# Demo_Board_4_-_Schematic.net
KiCad netlist of a schematic drawn in Altium Designer
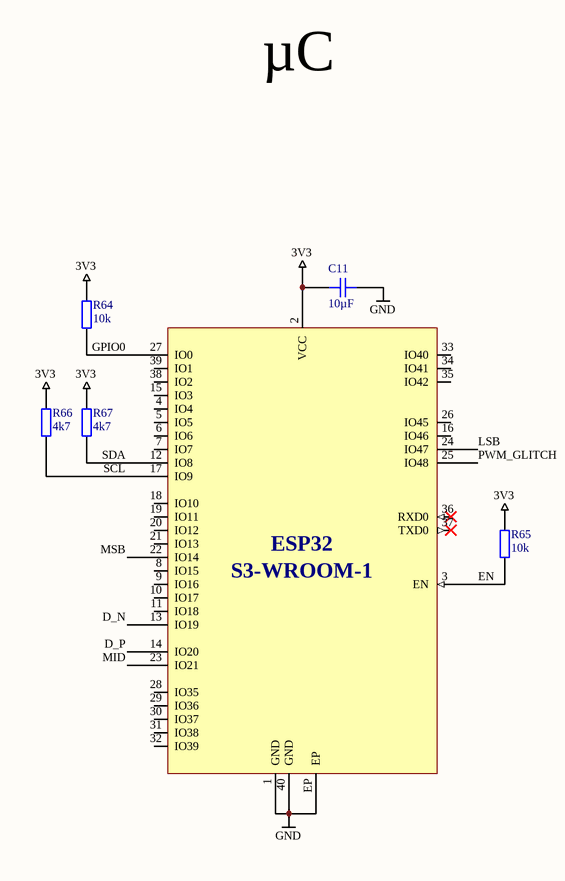
[diagram p0: Demo Board 4 - Schematic.SchDoc]

(export (version "E")
  (design (tool "Eeschema 10.0.6"))
  (components
    (comp (ref "C11")
      (value "10µF")
      (footprint "CAP_0805")
      (description "Capacitor SMD 0805")
      (libsource (lib "Auer Library") (part "CAP_0805"))
    )
    (comp (ref "R64")
      (value "10k")
      (footprint "RES_0603")
      (description "Resistor SMD 0603")
      (libsource (lib "Auer Library") (part "RES_0603"))
    )
    (comp (ref "R65")
      (value "10k")
      (footprint "RES_0603")
      (description "Resistor SMD 0603")
      (libsource (lib "Auer Library") (part "RES_0603"))
    )
    (comp (ref "R66")
      (value "4k7")
      (footprint "RES_0603")
      (description "Resistor SMD 0603")
      (libsource (lib "Auer Library") (part "RES_0603"))
    )
    (comp (ref "R67")
      (value "4k7")
      (footprint "RES_0603")
      (description "Resistor SMD 0603")
      (libsource (lib "Auer Library") (part "RES_0603"))
    )
    (comp (ref "U3")
      (value "ESP32-S3-WROOM-1-N8")
      (footprint "ESP32-S3-WROOM-1")
      (fields
        (field (name "MANUFACTURER") "Espressif")
        (field (name "MANUFACTURER PART NUMBER") "ESP32-S3-WROOM-1-N4")
      )
      (libsource (lib "Auer Library") (part "ESP32-S3-WROOM-1-N4"))
    )
  )
  (nets
    (net (code "1") (name "/D_N") (class "Default")
      (node (ref "U3") (pin "13") (pinfunction "IO19_13") (pintype "bidirectional"))
    )
    (net (code "2") (name "/D_P") (class "Default")
      (node (ref "U3") (pin "14") (pinfunction "IO20_14") (pintype "bidirectional"))
    )
    (net (code "3") (name "/EN") (class "Default")
      (node (ref "R65") (pin "1") (pinfunction "1_1") (pintype "passive"))
      (node (ref "U3") (pin "3") (pinfunction "EN_3") (pintype "input"))
    )
    (net (code "4") (name "/GPIO0") (class "Default")
      (node (ref "R64") (pin "1") (pinfunction "1_1") (pintype "passive"))
      (node (ref "U3") (pin "27") (pinfunction "IO0_27") (pintype "bidirectional"))
    )
    (net (code "5") (name "/LSB") (class "Default")
      (node (ref "U3") (pin "24") (pinfunction "IO47_24") (pintype "bidirectional"))
    )
    (net (code "6") (name "/MID") (class "Default")
      (node (ref "U3") (pin "23") (pinfunction "IO21_23") (pintype "bidirectional"))
    )
    (net (code "7") (name "/MSB") (class "Default")
      (node (ref "U3") (pin "22") (pinfunction "IO14_22") (pintype "bidirectional"))
    )
    (net (code "8") (name "/PWM_GLITCH") (class "Default")
      (node (ref "U3") (pin "25") (pinfunction "IO48_25") (pintype "bidirectional"))
    )
    (net (code "9") (name "/SCL") (class "Default")
      (node (ref "R66") (pin "1") (pinfunction "1_1") (pintype "passive"))
      (node (ref "U3") (pin "17") (pinfunction "IO9_17") (pintype "bidirectional"))
    )
    (net (code "10") (name "/SDA") (class "Default")
      (node (ref "R67") (pin "1") (pinfunction "1_1") (pintype "passive"))
      (node (ref "U3") (pin "12") (pinfunction "IO8_12") (pintype "bidirectional"))
    )
    (net (code "11") (name "3V3") (class "Default")
      (node (ref "C11") (pin "2") (pinfunction "2_2") (pintype "passive"))
      (node (ref "R64") (pin "2") (pinfunction "2_2") (pintype "passive"))
      (node (ref "R65") (pin "2") (pinfunction "2_2") (pintype "passive"))
      (node (ref "R66") (pin "2") (pinfunction "2_2") (pintype "passive"))
      (node (ref "R67") (pin "2") (pinfunction "2_2") (pintype "passive"))
      (node (ref "U3") (pin "2") (pinfunction "VCC_2") (pintype "power_in"))
    )
    (net (code "12") (name "GND") (class "Default")
      (node (ref "C11") (pin "1") (pinfunction "1_1") (pintype "passive"))
      (node (ref "U3") (pin "1") (pinfunction "GND_1") (pintype "power_in"))
      (node (ref "U3") (pin "40") (pinfunction "GND_40") (pintype "power_in"))
      (node (ref "U3") (pin "EP") (pinfunction "EP_EP") (pintype "power_in"))
    )
    (net (code "13") (name "unconnected-(U3-IO1-Pad39)") (class "Default")
      (node (ref "U3") (pin "39") (pinfunction "IO1_39") (pintype "bidirectional"))
    )
    (net (code "14") (name "unconnected-(U3-IO2-Pad38)") (class "Default")
      (node (ref "U3") (pin "38") (pinfunction "IO2_38") (pintype "bidirectional"))
    )
    (net (code "15") (name "unconnected-(U3-IO3-Pad15)") (class "Default")
      (node (ref "U3") (pin "15") (pinfunction "IO3_15") (pintype "bidirectional"))
    )
    (net (code "16") (name "unconnected-(U3-IO4-Pad4)") (class "Default")
      (node (ref "U3") (pin "4") (pinfunction "IO4_4") (pintype "bidirectional"))
    )
    (net (code "17") (name "unconnected-(U3-IO5-Pad5)") (class "Default")
      (node (ref "U3") (pin "5") (pinfunction "IO5_5") (pintype "bidirectional"))
    )
    (net (code "18") (name "unconnected-(U3-IO6-Pad6)") (class "Default")
      (node (ref "U3") (pin "6") (pinfunction "IO6_6") (pintype "bidirectional"))
    )
    (net (code "19") (name "unconnected-(U3-IO7-Pad7)") (class "Default")
      (node (ref "U3") (pin "7") (pinfunction "IO7_7") (pintype "bidirectional"))
    )
    (net (code "20") (name "unconnected-(U3-IO10-Pad18)") (class "Default")
      (node (ref "U3") (pin "18") (pinfunction "IO10_18") (pintype "bidirectional"))
    )
    (net (code "21") (name "unconnected-(U3-IO11-Pad19)") (class "Default")
      (node (ref "U3") (pin "19") (pinfunction "IO11_19") (pintype "bidirectional"))
    )
    (net (code "22") (name "unconnected-(U3-IO12-Pad20)") (class "Default")
      (node (ref "U3") (pin "20") (pinfunction "IO12_20") (pintype "bidirectional"))
    )
    (net (code "23") (name "unconnected-(U3-IO13-Pad21)") (class "Default")
      (node (ref "U3") (pin "21") (pinfunction "IO13_21") (pintype "bidirectional"))
    )
    (net (code "24") (name "unconnected-(U3-IO15-Pad8)") (class "Default")
      (node (ref "U3") (pin "8") (pinfunction "IO15_8") (pintype "bidirectional"))
    )
    (net (code "25") (name "unconnected-(U3-IO16-Pad9)") (class "Default")
      (node (ref "U3") (pin "9") (pinfunction "IO16_9") (pintype "bidirectional"))
    )
    (net (code "26") (name "unconnected-(U3-IO17-Pad10)") (class "Default")
      (node (ref "U3") (pin "10") (pinfunction "IO17_10") (pintype "bidirectional"))
    )
    (net (code "27") (name "unconnected-(U3-IO18-Pad11)") (class "Default")
      (node (ref "U3") (pin "11") (pinfunction "IO18_11") (pintype "bidirectional"))
    )
    (net (code "28") (name "unconnected-(U3-IO35-Pad28)") (class "Default")
      (node (ref "U3") (pin "28") (pinfunction "IO35_28") (pintype "bidirectional"))
    )
    (net (code "29") (name "unconnected-(U3-IO36-Pad29)") (class "Default")
      (node (ref "U3") (pin "29") (pinfunction "IO36_29") (pintype "bidirectional"))
    )
    (net (code "30") (name "unconnected-(U3-IO37-Pad30)") (class "Default")
      (node (ref "U3") (pin "30") (pinfunction "IO37_30") (pintype "bidirectional"))
    )
    (net (code "31") (name "unconnected-(U3-IO38-Pad31)") (class "Default")
      (node (ref "U3") (pin "31") (pinfunction "IO38_31") (pintype "bidirectional"))
    )
    (net (code "32") (name "unconnected-(U3-IO39-Pad32)") (class "Default")
      (node (ref "U3") (pin "32") (pinfunction "IO39_32") (pintype "bidirectional"))
    )
    (net (code "33") (name "unconnected-(U3-IO40-Pad33)") (class "Default")
      (node (ref "U3") (pin "33") (pinfunction "IO40_33") (pintype "bidirectional"))
    )
    (net (code "34") (name "unconnected-(U3-IO41-Pad34)") (class "Default")
      (node (ref "U3") (pin "34") (pinfunction "IO41_34") (pintype "bidirectional"))
    )
    (net (code "35") (name "unconnected-(U3-IO42-Pad35)") (class "Default")
      (node (ref "U3") (pin "35") (pinfunction "IO42_35") (pintype "bidirectional"))
    )
    (net (code "36") (name "unconnected-(U3-IO45-Pad26)") (class "Default")
      (node (ref "U3") (pin "26") (pinfunction "IO45_26") (pintype "bidirectional"))
    )
    (net (code "37") (name "unconnected-(U3-IO46-Pad16)") (class "Default")
      (node (ref "U3") (pin "16") (pinfunction "IO46_16") (pintype "bidirectional"))
    )
    (net (code "38") (name "unconnected-(U3-RXD0-Pad36)") (class "Default")
      (node (ref "U3") (pin "36") (pinfunction "RXD0_36") (pintype "input+no_connect"))
    )
    (net (code "39") (name "unconnected-(U3-TXD0-Pad37)") (class "Default")
      (node (ref "U3") (pin "37") (pinfunction "TXD0_37") (pintype "output+no_connect"))
    )
  )
)
